# Amplifier.net
KiCad netlist of a schematic drawn in Altium Designer
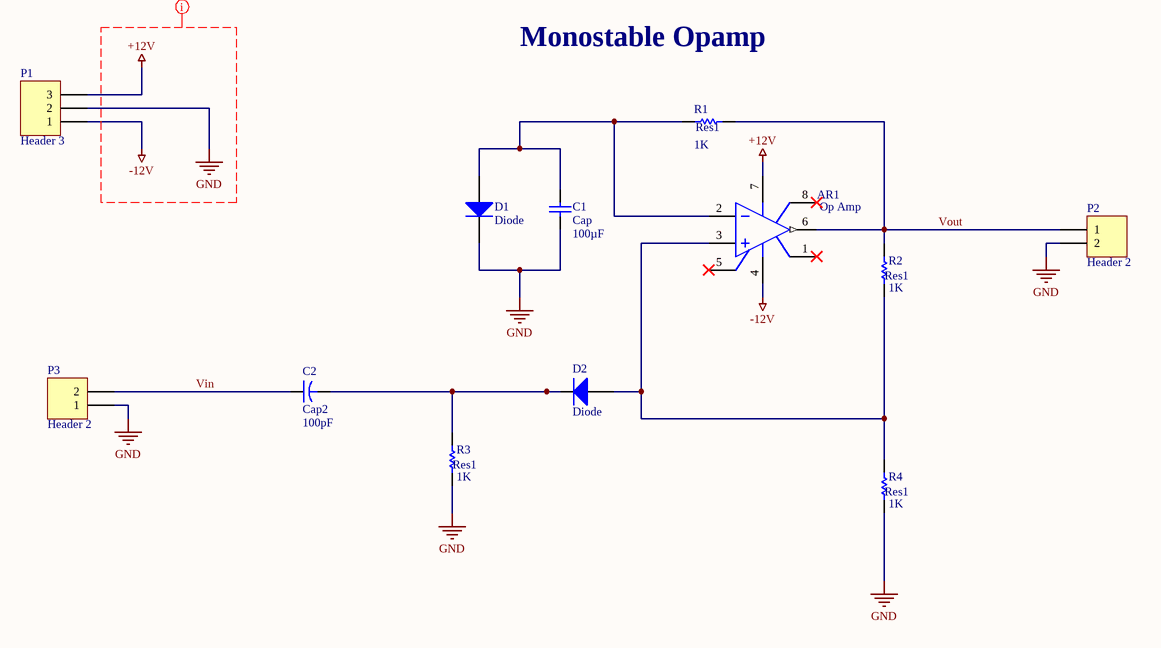
[diagram p0: Amplifier.SchDoc]

(export (version "E")
  (design (tool "Eeschema 10.0.6"))
  (components
    (comp (ref "AR1")
      (value "Op Amp")
      (footprint "H-08A")
      (description "FET Operational Amplifier")
      (fields (field (name "PUBLISHER") "Altium Limited"))
      (libsource (lib "Miscellaneous Devices") (part "Op Amp"))
    )
    (comp (ref "C1")
      (value "Cap")
      (footprint "RAD-0.3")
      (description "Capacitor")
      (fields (field (name "ALTIUM_VALUE") "100µF") (field (name "PUBLISHER") "Altium Limited"))
      (libsource (lib "Miscellaneous Devices") (part "Cap"))
    )
    (comp (ref "C2")
      (value "Cap2")
      (footprint "CAPR5-4X5")
      (description "Capacitor")
      (fields (field (name "ALTIUM_VALUE") "100pF") (field (name "PUBLISHER") "Altium Limited"))
      (libsource (lib "Miscellaneous Devices") (part "Cap2"))
    )
    (comp (ref "D1")
      (value "Diode")
      (footprint "SMC")
      (description "Default Diode")
      (fields (field (name "PUBLISHER") "Altium Limited"))
      (libsource (lib "Miscellaneous Devices") (part "Diode"))
    )
    (comp (ref "D2")
      (value "Diode")
      (footprint "SMC")
      (description "Default Diode")
      (fields (field (name "PUBLISHER") "Altium Limited"))
      (libsource (lib "Miscellaneous Devices") (part "Diode"))
    )
    (comp (ref "P1")
      (value "Header 3")
      (footprint "HDR1X3")
      (description "Header, 3-Pin")
      (fields (field (name "PUBLISHER") "Altium Limited"))
      (libsource (lib "Miscellaneous Connectors") (part "Header 3"))
    )
    (comp (ref "P2")
      (value "Header 2")
      (footprint "HDR1X2")
      (description "Header, 2-Pin")
      (fields (field (name "PUBLISHER") "Altium Limited"))
      (libsource (lib "Miscellaneous Connectors") (part "Header 2"))
    )
    (comp (ref "P3")
      (value "Header 2")
      (footprint "HDR1X2")
      (description "Header, 2-Pin")
      (fields (field (name "PUBLISHER") "Altium Limited"))
      (libsource (lib "") (part "Header 2_1"))
    )
    (comp (ref "R1")
      (value "Res1")
      (footprint "AXIAL-0.3")
      (description "Resistor")
      (fields (field (name "ALTIUM_VALUE") "1K") (field (name "PUBLISHER") "Altium Limited"))
      (libsource (lib "Miscellaneous Devices") (part "Res1"))
    )
    (comp (ref "R2")
      (value "Res1")
      (footprint "AXIAL-0.3")
      (description "Resistor")
      (fields (field (name "ALTIUM_VALUE") "1K") (field (name "PUBLISHER") "Altium Limited"))
      (libsource (lib "Miscellaneous Devices") (part "Res1"))
    )
    (comp (ref "R3")
      (value "Res1")
      (footprint "AXIAL-0.3")
      (description "Resistor")
      (fields (field (name "ALTIUM_VALUE") "1K") (field (name "PUBLISHER") "Altium Limited"))
      (libsource (lib "Miscellaneous Devices") (part "Res1"))
    )
    (comp (ref "R4")
      (value "Res1")
      (footprint "AXIAL-0.3")
      (description "Resistor")
      (fields (field (name "ALTIUM_VALUE") "1K") (field (name "PUBLISHER") "Altium Limited"))
      (libsource (lib "Miscellaneous Devices") (part "Res1"))
    )
  )
  (nets
    (net (code "1") (name "+12V") (class "Default")
      (node (ref "AR1") (pin "7") (pinfunction "V+_7") (pintype "power_in"))
      (node (ref "P1") (pin "3") (pinfunction "3_3") (pintype "passive"))
    )
    (net (code "2") (name "-12V") (class "Default")
      (node (ref "AR1") (pin "4") (pinfunction "V-_4") (pintype "power_in"))
      (node (ref "P1") (pin "1") (pinfunction "1_1") (pintype "passive"))
    )
    (net (code "3") (name "/Vin") (class "Default")
      (node (ref "C2") (pin "1") (pinfunction "1_1") (pintype "passive"))
      (node (ref "P3") (pin "2") (pinfunction "2_2") (pintype "passive"))
    )
    (net (code "4") (name "/Vout") (class "Default")
      (node (ref "AR1") (pin "6") (pinfunction "OUT_6") (pintype "output"))
      (node (ref "P2") (pin "1") (pinfunction "1_1") (pintype "passive"))
      (node (ref "R1") (pin "2") (pinfunction "2_2") (pintype "passive"))
      (node (ref "R2") (pin "1") (pinfunction "1_1") (pintype "passive"))
    )
    (net (code "5") (name "GND") (class "Default")
      (node (ref "C1") (pin "2") (pinfunction "2_2") (pintype "passive"))
      (node (ref "D1") (pin "2") (pinfunction "K_2") (pintype "passive"))
      (node (ref "P1") (pin "2") (pinfunction "2_2") (pintype "passive"))
      (node (ref "P2") (pin "2") (pinfunction "2_2") (pintype "passive"))
      (node (ref "P3") (pin "1") (pinfunction "1_1") (pintype "passive"))
      (node (ref "R3") (pin "2") (pinfunction "2_2") (pintype "passive"))
      (node (ref "R4") (pin "2") (pinfunction "2_2") (pintype "passive"))
    )
    (net (code "6") (name "Net-(AR1-IN+)") (class "Default")
      (node (ref "AR1") (pin "3") (pinfunction "IN+_3") (pintype "passive"))
      (node (ref "D2") (pin "1") (pinfunction "A_1") (pintype "passive"))
      (node (ref "R2") (pin "2") (pinfunction "2_2") (pintype "passive"))
      (node (ref "R4") (pin "1") (pinfunction "1_1") (pintype "passive"))
    )
    (net (code "7") (name "Net-(AR1-IN-)") (class "Default")
      (node (ref "AR1") (pin "2") (pinfunction "IN-_2") (pintype "passive"))
      (node (ref "C1") (pin "1") (pinfunction "1_1") (pintype "passive"))
      (node (ref "D1") (pin "1") (pinfunction "A_1") (pintype "passive"))
      (node (ref "R1") (pin "1") (pinfunction "1_1") (pintype "passive"))
    )
    (net (code "8") (name "Net-(D2-K)") (class "Default")
      (node (ref "C2") (pin "2") (pinfunction "2_2") (pintype "passive"))
      (node (ref "D2") (pin "2") (pinfunction "K_2") (pintype "passive"))
      (node (ref "R3") (pin "1") (pinfunction "1_1") (pintype "passive"))
    )
    (net (code "9") (name "unconnected-(AR1-OS_NUL-Pad1)") (class "Default")
      (node (ref "AR1") (pin "1") (pinfunction "OS_NUL_1") (pintype "passive+no_connect"))
    )
    (net (code "10") (name "unconnected-(AR1-OS_NUL-Pad5)") (class "Default")
      (node (ref "AR1") (pin "5") (pinfunction "OS_NUL_5") (pintype "passive+no_connect"))
    )
    (net (code "11") (name "unconnected-(AR1-TAB-Pad8)") (class "Default")
      (node (ref "AR1") (pin "8") (pinfunction "TAB_8") (pintype "passive+no_connect"))
    )
  )
)
